# Adafruit_QT_Py_ESP32-S2.net
KiCad netlist of a schematic drawn in EAGLE
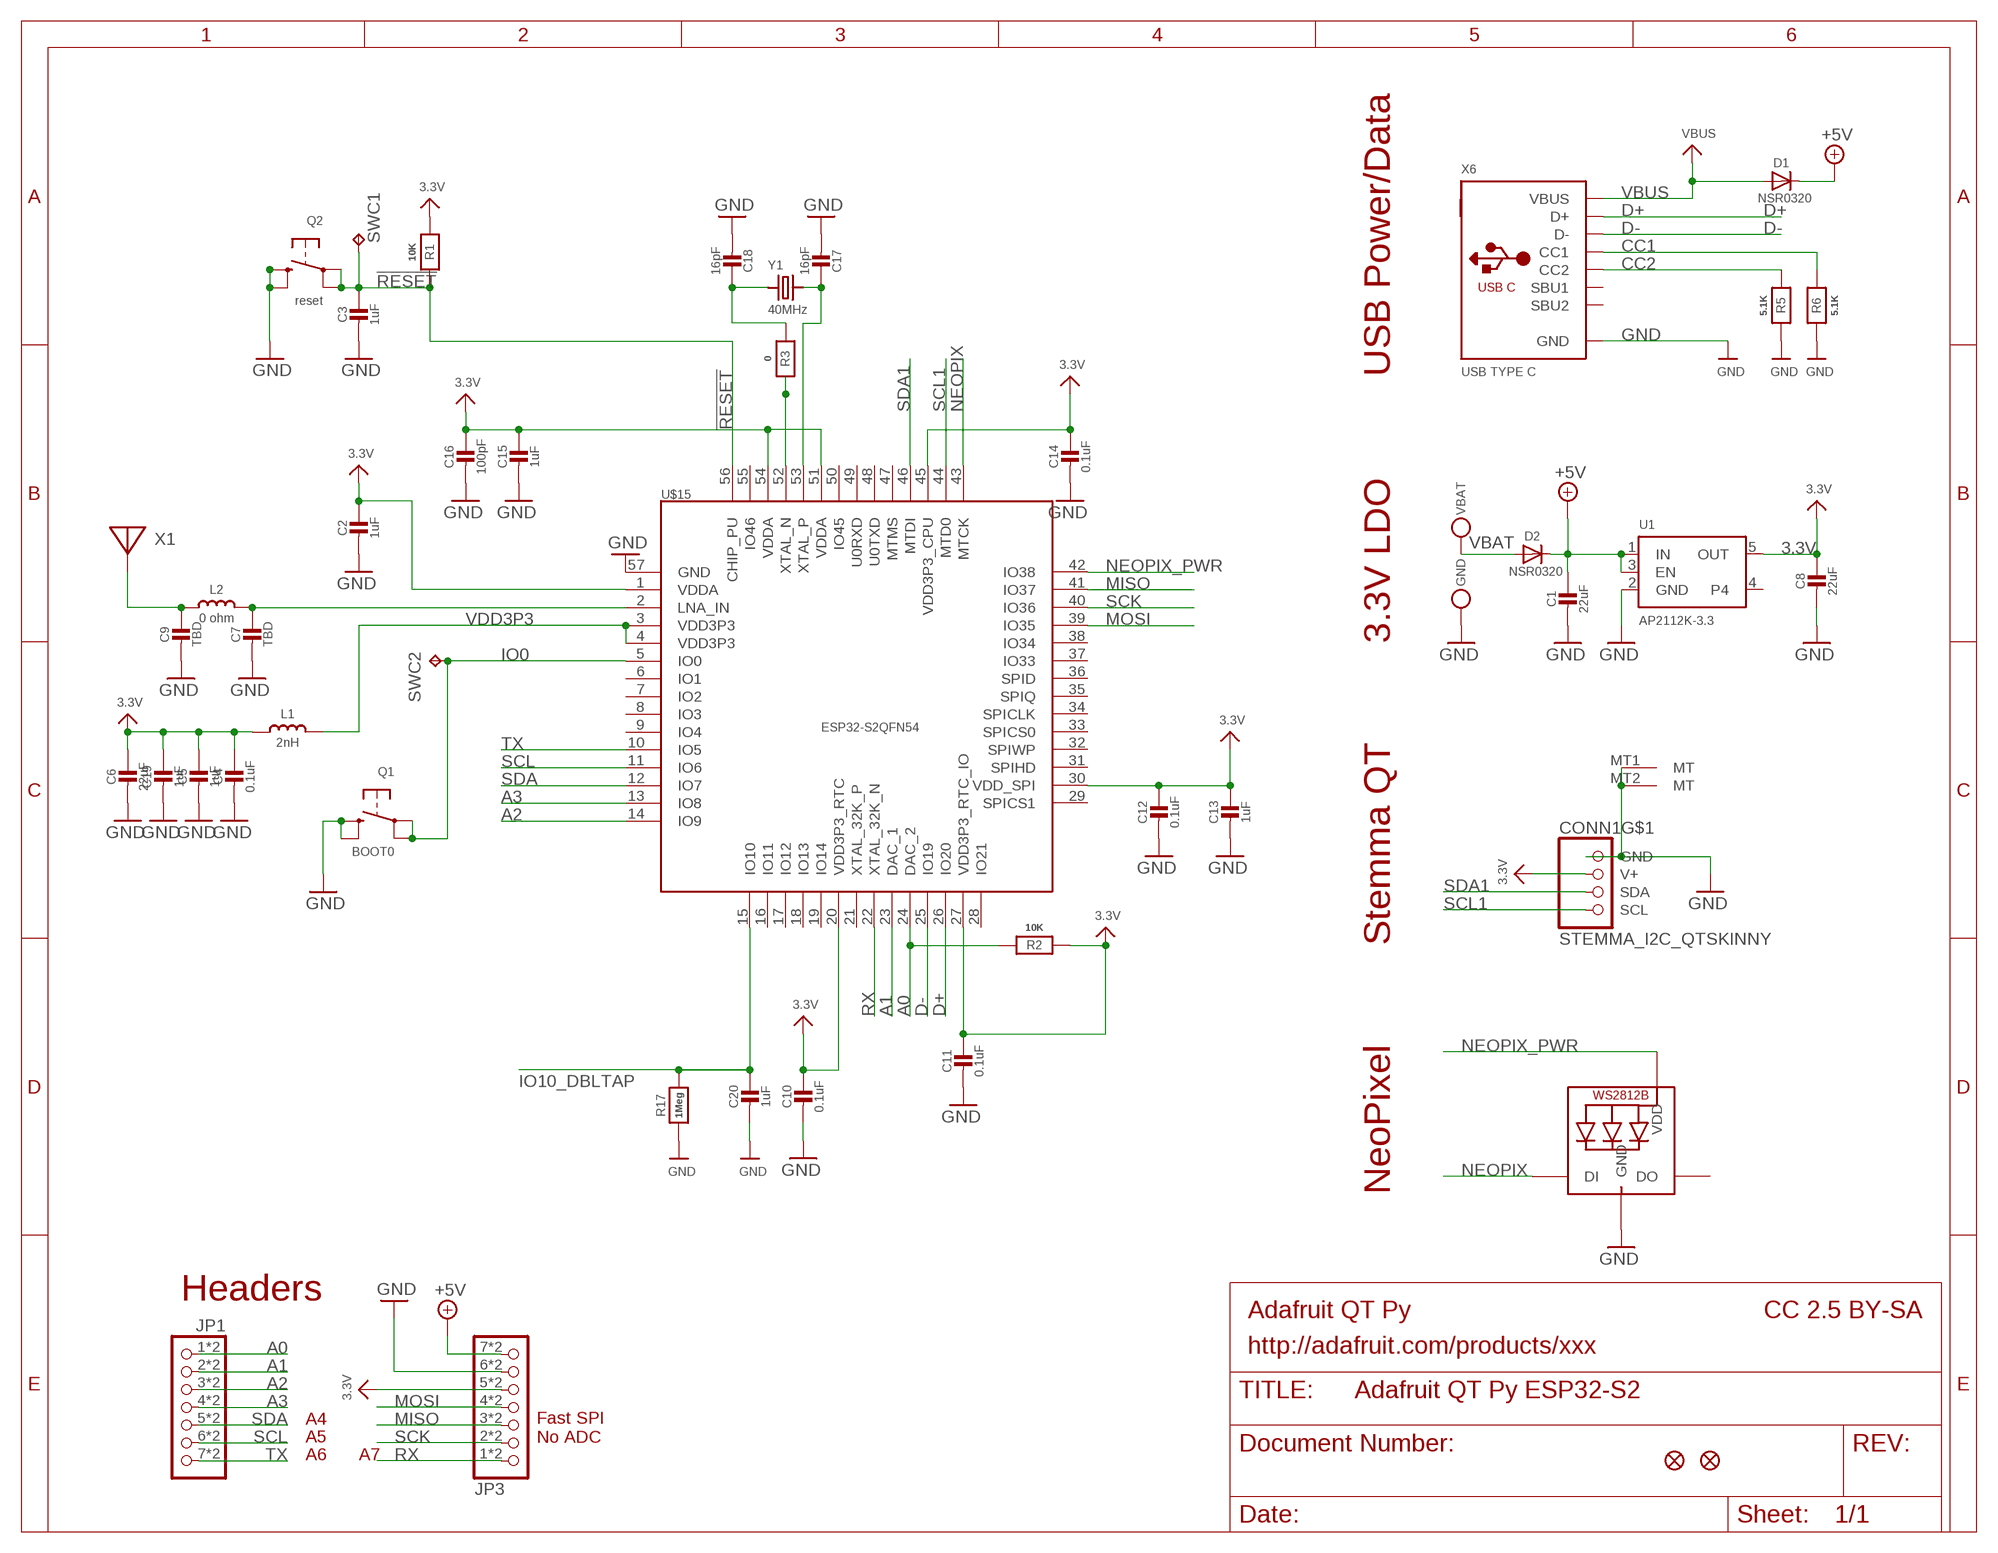
[diagram p0: schematic, sheet 1]

(export (version "E")
  (design (tool "Eeschema 10.0.6"))
  (components
    (comp (ref "C1")
      (value "22uF")
      (footprint "eagle-import:0805-NO")
      (libsource (lib "eagle-import") (part "CAP_CERAMIC0805-NOOUTLINE"))
    )
    (comp (ref "C2")
      (value "1uF")
      (footprint "eagle-import:_0402NO")
      (libsource (lib "eagle-import") (part "CAP_CERAMIC_0402NO"))
    )
    (comp (ref "C3")
      (value "1uF")
      (footprint "eagle-import:_0402NO")
      (libsource (lib "eagle-import") (part "CAP_CERAMIC_0402NO"))
    )
    (comp (ref "C4")
      (value "0.1uF")
      (footprint "eagle-import:_0402NO")
      (libsource (lib "eagle-import") (part "CAP_CERAMIC_0402NO"))
    )
    (comp (ref "C5")
      (value "1uF")
      (footprint "eagle-import:_0402NO")
      (libsource (lib "eagle-import") (part "CAP_CERAMIC_0402NO"))
    )
    (comp (ref "C6")
      (value "22uF")
      (footprint "eagle-import:0805-NO")
      (libsource (lib "eagle-import") (part "CAP_CERAMIC0805-NOOUTLINE"))
    )
    (comp (ref "C7")
      (value "TBD")
      (footprint "eagle-import:_0402NO")
      (libsource (lib "eagle-import") (part "CAP_CERAMIC_0402NO"))
    )
    (comp (ref "C8")
      (value "22uF")
      (footprint "eagle-import:0805-NO")
      (libsource (lib "eagle-import") (part "CAP_CERAMIC0805-NOOUTLINE"))
    )
    (comp (ref "C9")
      (value "TBD")
      (footprint "eagle-import:_0402NO")
      (libsource (lib "eagle-import") (part "CAP_CERAMIC_0402NO"))
    )
    (comp (ref "C10")
      (value "0.1uF")
      (footprint "eagle-import:_0402NO")
      (libsource (lib "eagle-import") (part "CAP_CERAMIC_0402NO"))
    )
    (comp (ref "C11")
      (value "0.1uF")
      (footprint "eagle-import:_0402NO")
      (libsource (lib "eagle-import") (part "CAP_CERAMIC_0402NO"))
    )
    (comp (ref "C12")
      (value "0.1uF")
      (footprint "eagle-import:_0402NO")
      (libsource (lib "eagle-import") (part "CAP_CERAMIC_0402NO"))
    )
    (comp (ref "C13")
      (value "1uF")
      (footprint "eagle-import:_0402NO")
      (libsource (lib "eagle-import") (part "CAP_CERAMIC_0402NO"))
    )
    (comp (ref "C14")
      (value "0.1uF")
      (footprint "eagle-import:_0402NO")
      (libsource (lib "eagle-import") (part "CAP_CERAMIC_0402NO"))
    )
    (comp (ref "C15")
      (value "1uF")
      (footprint "eagle-import:_0402NO")
      (libsource (lib "eagle-import") (part "CAP_CERAMIC_0402NO"))
    )
    (comp (ref "C16")
      (value "100pF")
      (footprint "eagle-import:_0402NO")
      (libsource (lib "eagle-import") (part "CAP_CERAMIC_0402NO"))
    )
    (comp (ref "C17")
      (value "16pF")
      (footprint "eagle-import:_0402NO")
      (libsource (lib "eagle-import") (part "CAP_CERAMIC_0402NO"))
    )
    (comp (ref "C18")
      (value "16pF")
      (footprint "eagle-import:_0402NO")
      (libsource (lib "eagle-import") (part "CAP_CERAMIC_0402NO"))
    )
    (comp (ref "C19")
      (value "1uF")
      (footprint "eagle-import:_0402NO")
      (libsource (lib "eagle-import") (part "CAP_CERAMIC_0402NO"))
    )
    (comp (ref "C20")
      (value "1uF")
      (footprint "eagle-import:_0402NO")
      (libsource (lib "eagle-import") (part "CAP_CERAMIC_0402NO"))
    )
    (comp (ref "CONN1")
      (value "STEMMA_I2C_QTSKINNY")
      (footprint "eagle-import:JST_SH4_SKINNY")
      (libsource (lib "eagle-import") (part "STEMMA_I2C_QTSKINNY"))
    )
    (comp (ref "D1")
      (value "NSR0320")
      (footprint "eagle-import:SOD-323_MINI")
      (libsource (lib "eagle-import") (part "DIODE_SOD323MINI"))
    )
    (comp (ref "D2")
      (value "NSR0320")
      (footprint "eagle-import:SOD-323_MINI")
      (libsource (lib "eagle-import") (part "DIODE_SOD323MINI"))
    )
    (comp (ref "GND")
      (value "TESTPOINT_1X3")
      (footprint "eagle-import:TESTPOINT_RECT_1X3MM")
      (libsource (lib "eagle-import") (part "TESTPOINT_1X3"))
    )
    (comp (ref "JP1")
      (value "HEADER-1X7_CASTEL")
      (footprint "eagle-import:1X07_CASTEL")
      (libsource (lib "eagle-import") (part "HEADER-1X7_CASTEL"))
    )
    (comp (ref "JP3")
      (value "HEADER-1X7_CASTEL")
      (footprint "eagle-import:1X07_CASTEL")
      (libsource (lib "eagle-import") (part "HEADER-1X7_CASTEL"))
    )
    (comp (ref "L1")
      (value "2nH")
      (footprint "eagle-import:_0402")
      (libsource (lib "eagle-import") (part "INDUCTOR_0402"))
    )
    (comp (ref "L2")
      (value "0 ohm")
      (footprint "eagle-import:_0402")
      (libsource (lib "eagle-import") (part "INDUCTOR_0402"))
    )
    (comp (ref "LED1")
      (value "WS2812B_SK6805_1515")
      (footprint "eagle-import:SK6805_1515")
      (libsource (lib "eagle-import") (part "WS2812B_SK6805_1515"))
    )
    (comp (ref "Q1")
      (value "BOOT0")
      (footprint "eagle-import:BTN_KMR2_4.6X2.8")
      (libsource (lib "eagle-import") (part "SWITCH_TACT_SMT4.6X2.8"))
    )
    (comp (ref "Q2")
      (value "reset")
      (footprint "eagle-import:BTN_KMR2_4.6X2.8")
      (libsource (lib "eagle-import") (part "SWITCH_TACT_SMT4.6X2.8"))
    )
    (comp (ref "R1")
      (value "10K")
      (footprint "eagle-import:_0402NO")
      (libsource (lib "eagle-import") (part "RESISTOR_0402NO"))
    )
    (comp (ref "R2")
      (value "10K")
      (footprint "eagle-import:_0402NO")
      (libsource (lib "eagle-import") (part "RESISTOR_0402NO"))
    )
    (comp (ref "R3")
      (value "0")
      (footprint "eagle-import:_0402NO")
      (libsource (lib "eagle-import") (part "RESISTOR_0402NO"))
    )
    (comp (ref "R5")
      (value "5.1K")
      (footprint "eagle-import:_0402NO")
      (libsource (lib "eagle-import") (part "RESISTOR_0402NO"))
    )
    (comp (ref "R6")
      (value "5.1K")
      (footprint "eagle-import:_0402NO")
      (libsource (lib "eagle-import") (part "RESISTOR_0402NO"))
    )
    (comp (ref "R17")
      (value "1Meg")
      (footprint "eagle-import:_0402NO")
      (libsource (lib "eagle-import") (part "RESISTOR_0402NO"))
    )
    (comp (ref "SWC1")
      (value "TPB1,27")
      (footprint "eagle-import:B1,27")
      (libsource (lib "eagle-import") (part "TPB1,27"))
    )
    (comp (ref "SWC2")
      (value "TPB1,27")
      (footprint "eagle-import:B1,27")
      (libsource (lib "eagle-import") (part "TPB1,27"))
    )
    (comp (ref "U$6")
      (value "FIDUCIAL_1MM")
      (footprint "eagle-import:FIDUCIAL_1MM")
      (libsource (lib "eagle-import") (part "FIDUCIAL_1MM"))
    )
    (comp (ref "U$8")
      (value "FIDUCIAL_1MM")
      (footprint "eagle-import:FIDUCIAL_1MM")
      (libsource (lib "eagle-import") (part "FIDUCIAL_1MM"))
    )
    (comp (ref "U$15")
      (value "ESP32-S2QFN54")
      (footprint "eagle-import:QFN40P700X700X90-57T400N")
      (fields
        (field (name "DIGI-KEY_PART_NUMBER") "1965-ESP32-S2CT-ND")
        (field (name "MF") "Espressif Systems")
        (field (name "MP") "ESP32-S2")
      )
      (libsource (lib "eagle-import") (part "ESP32-S2QFN54"))
    )
    (comp (ref "U1")
      (value "AP2112K-3.3")
      (footprint "eagle-import:SOT23-5")
      (libsource (lib "eagle-import") (part "VREG_SOT23-5"))
    )
    (comp (ref "VBAT")
      (value "TESTPOINT_1X3")
      (footprint "eagle-import:TESTPOINT_RECT_1X3MM")
      (libsource (lib "eagle-import") (part "TESTPOINT_1X3"))
    )
    (comp (ref "X1")
      (value "ANTENNA_JOHANSON_2450AT18B100")
      (footprint "eagle-import:ANT_2450AT18B100")
      (libsource (lib "eagle-import") (part "ANTENNA_JOHANSON_2450AT18B100"))
    )
    (comp (ref "X6")
      (value "USB TYPE C")
      (footprint "eagle-import:USB_C_CUSB31-CFM2AX-01-X")
      (libsource (lib "eagle-import") (part "USB_C"))
    )
    (comp (ref "Y1")
      (value "40MHz")
      (footprint "eagle-import:CRYSTAL_2X1.6")
      (libsource (lib "eagle-import") (part "CRYSTAL_2X1.6MM"))
    )
  )
  (nets
    (net (code "1") (name "+5V") (class "Default")
      (node (ref "C1") (pin "1") (pinfunction "1_1") (pintype "passive"))
      (node (ref "D1") (pin "C") (pinfunction "C_C") (pintype "passive"))
      (node (ref "D2") (pin "C") (pinfunction "C_C") (pintype "passive"))
      (node (ref "JP3") (pin "7") (pinfunction "7_7") (pintype "passive"))
      (node (ref "JP3") (pin "7C") (pinfunction "7_7C") (pintype "passive"))
      (node (ref "U1") (pin "1") (pinfunction "IN_1") (pintype "power_in"))
      (node (ref "U1") (pin "3") (pinfunction "EN_3") (pintype "input"))
    )
    (net (code "2") (name "/A0") (class "Default")
      (node (ref "JP1") (pin "1") (pinfunction "1_1") (pintype "passive"))
      (node (ref "JP1") (pin "1C") (pinfunction "1_1C") (pintype "passive"))
      (node (ref "R2") (pin "2") (pinfunction "2_2") (pintype "passive"))
      (node (ref "U$15") (pin "24") (pinfunction "DAC_2_24") (pintype "bidirectional"))
    )
    (net (code "3") (name "/A1") (class "Default")
      (node (ref "JP1") (pin "2") (pinfunction "2_2") (pintype "passive"))
      (node (ref "JP1") (pin "2C") (pinfunction "2_2C") (pintype "passive"))
      (node (ref "U$15") (pin "23") (pinfunction "DAC_1_23") (pintype "bidirectional"))
    )
    (net (code "4") (name "/A2") (class "Default")
      (node (ref "JP1") (pin "3") (pinfunction "3_3") (pintype "passive"))
      (node (ref "JP1") (pin "3C") (pinfunction "3_3C") (pintype "passive"))
      (node (ref "U$15") (pin "14") (pinfunction "IO9_14") (pintype "bidirectional"))
    )
    (net (code "5") (name "/A3") (class "Default")
      (node (ref "JP1") (pin "4") (pinfunction "4_4") (pintype "passive"))
      (node (ref "JP1") (pin "4C") (pinfunction "4_4C") (pintype "passive"))
      (node (ref "U$15") (pin "13") (pinfunction "IO8_13") (pintype "bidirectional"))
    )
    (net (code "6") (name "/CC1") (class "Default")
      (node (ref "R6") (pin "2") (pinfunction "2_2") (pintype "passive"))
      (node (ref "X6") (pin "A5") (pinfunction "CC1_A5") (pintype "bidirectional"))
    )
    (net (code "7") (name "/CC2") (class "Default")
      (node (ref "R5") (pin "2") (pinfunction "2_2") (pintype "passive"))
      (node (ref "X6") (pin "B5") (pinfunction "CC2_B5") (pintype "bidirectional"))
    )
    (net (code "8") (name "/D+") (class "Default")
      (node (ref "U$15") (pin "26") (pinfunction "IO20_26") (pintype "bidirectional"))
      (node (ref "X6") (pin "A6") (pinfunction "D+_A6") (pintype "bidirectional"))
      (node (ref "X6") (pin "B6") (pinfunction "D+_B6") (pintype "bidirectional"))
    )
    (net (code "9") (name "/D-") (class "Default")
      (node (ref "U$15") (pin "25") (pinfunction "IO19_25") (pintype "bidirectional"))
      (node (ref "X6") (pin "A7") (pinfunction "D-_A7") (pintype "bidirectional"))
      (node (ref "X6") (pin "B7") (pinfunction "D-_B7") (pintype "bidirectional"))
    )
    (net (code "10") (name "/IO0") (class "Default")
      (node (ref "Q1") (pin "A") (pinfunction "P_A") (pintype "passive"))
      (node (ref "Q1") (pin "A'") (pinfunction "P1_A'") (pintype "passive"))
      (node (ref "SWC2") (pin "TP") (pinfunction "TP_TP") (pintype "input"))
      (node (ref "U$15") (pin "5") (pinfunction "IO0_5") (pintype "bidirectional"))
    )
    (net (code "11") (name "/IO10_DBLTAP") (class "Default")
      (node (ref "C20") (pin "1") (pinfunction "1_1") (pintype "passive"))
      (node (ref "R17") (pin "2") (pinfunction "2_2") (pintype "passive"))
      (node (ref "U$15") (pin "15") (pinfunction "IO10_15") (pintype "bidirectional"))
    )
    (net (code "12") (name "/MISO") (class "Default")
      (node (ref "JP3") (pin "3") (pinfunction "3_3") (pintype "passive"))
      (node (ref "JP3") (pin "3C") (pinfunction "3_3C") (pintype "passive"))
      (node (ref "U$15") (pin "41") (pinfunction "IO37_41") (pintype "bidirectional"))
    )
    (net (code "13") (name "/MOSI") (class "Default")
      (node (ref "JP3") (pin "4") (pinfunction "4_4") (pintype "passive"))
      (node (ref "JP3") (pin "4C") (pinfunction "4_4C") (pintype "passive"))
      (node (ref "U$15") (pin "39") (pinfunction "IO35_39") (pintype "bidirectional"))
    )
    (net (code "14") (name "/NEOPIX") (class "Default")
      (node (ref "LED1") (pin "1") (pinfunction "DI_1") (pintype "input"))
      (node (ref "U$15") (pin "43") (pinfunction "MTCK_43") (pintype "bidirectional"))
    )
    (net (code "15") (name "/NEOPIX_PWR") (class "Default")
      (node (ref "LED1") (pin "2") (pinfunction "VDD_2") (pintype "power_in"))
      (node (ref "U$15") (pin "42") (pinfunction "IO38_42") (pintype "bidirectional"))
    )
    (net (code "16") (name "/RX") (class "Default")
      (node (ref "JP3") (pin "1") (pinfunction "1_1") (pintype "passive"))
      (node (ref "JP3") (pin "1C") (pinfunction "1_1C") (pintype "passive"))
      (node (ref "U$15") (pin "22") (pinfunction "XTAL_32K_N_22") (pintype "bidirectional"))
    )
    (net (code "17") (name "/SCK") (class "Default")
      (node (ref "JP3") (pin "2") (pinfunction "2_2") (pintype "passive"))
      (node (ref "JP3") (pin "2C") (pinfunction "2_2C") (pintype "passive"))
      (node (ref "U$15") (pin "40") (pinfunction "IO36_40") (pintype "bidirectional"))
    )
    (net (code "18") (name "/SCL") (class "Default")
      (node (ref "JP1") (pin "6") (pinfunction "6_6") (pintype "passive"))
      (node (ref "JP1") (pin "6C") (pinfunction "6_6C") (pintype "passive"))
      (node (ref "U$15") (pin "11") (pinfunction "IO6_11") (pintype "bidirectional"))
    )
    (net (code "19") (name "/SCL1") (class "Default")
      (node (ref "CONN1") (pin "4") (pinfunction "SCL_4") (pintype "passive"))
      (node (ref "U$15") (pin "44") (pinfunction "MTD0_44") (pintype "bidirectional"))
    )
    (net (code "20") (name "/SDA") (class "Default")
      (node (ref "JP1") (pin "5") (pinfunction "5_5") (pintype "passive"))
      (node (ref "JP1") (pin "5C") (pinfunction "5_5C") (pintype "passive"))
      (node (ref "U$15") (pin "12") (pinfunction "IO7_12") (pintype "bidirectional"))
    )
    (net (code "21") (name "/SDA1") (class "Default")
      (node (ref "CONN1") (pin "3") (pinfunction "SDA_3") (pintype "passive"))
      (node (ref "U$15") (pin "46") (pinfunction "MTDI_46") (pintype "bidirectional"))
    )
    (net (code "22") (name "/TX") (class "Default")
      (node (ref "JP1") (pin "7") (pinfunction "7_7") (pintype "passive"))
      (node (ref "JP1") (pin "7C") (pinfunction "7_7C") (pintype "passive"))
      (node (ref "U$15") (pin "10") (pinfunction "IO5_10") (pintype "bidirectional"))
    )
    (net (code "23") (name "/VBAT") (class "Default")
      (node (ref "D2") (pin "A") (pinfunction "A_A") (pintype "passive"))
      (node (ref "VBAT") (pin "P$1") (pinfunction "P$1_P$1") (pintype "bidirectional"))
    )
    (net (code "24") (name "/VDD3P3") (class "Default")
      (node (ref "L1") (pin "2") (pinfunction "2_2") (pintype "passive"))
      (node (ref "U$15") (pin "3") (pinfunction "VDD3P3_3") (pintype "power_in"))
      (node (ref "U$15") (pin "4") (pinfunction "VDD3P3_4") (pintype "power_in"))
    )
    (net (code "25") (name "/~{RESET}") (class "Default")
      (node (ref "C3") (pin "1") (pinfunction "1_1") (pintype "passive"))
      (node (ref "Q2") (pin "A") (pinfunction "P_A") (pintype "passive"))
      (node (ref "Q2") (pin "A'") (pinfunction "P1_A'") (pintype "passive"))
      (node (ref "R1") (pin "2") (pinfunction "2_2") (pintype "passive"))
      (node (ref "SWC1") (pin "TP") (pinfunction "TP_TP") (pintype "input"))
      (node (ref "U$15") (pin "56") (pinfunction "CHIP_PU_56") (pintype "input"))
    )
    (net (code "26") (name "3.3V") (class "Default")
      (node (ref "C10") (pin "1") (pinfunction "1_1") (pintype "passive"))
      (node (ref "C11") (pin "1") (pinfunction "1_1") (pintype "passive"))
      (node (ref "C12") (pin "1") (pinfunction "1_1") (pintype "passive"))
      (node (ref "C13") (pin "1") (pinfunction "1_1") (pintype "passive"))
      (node (ref "C14") (pin "1") (pinfunction "1_1") (pintype "passive"))
      (node (ref "C15") (pin "1") (pinfunction "1_1") (pintype "passive"))
      (node (ref "C16") (pin "1") (pinfunction "1_1") (pintype "passive"))
      (node (ref "C19") (pin "1") (pinfunction "1_1") (pintype "passive"))
      (node (ref "C2") (pin "1") (pinfunction "1_1") (pintype "passive"))
      (node (ref "C4") (pin "1") (pinfunction "1_1") (pintype "passive"))
      (node (ref "C5") (pin "1") (pinfunction "1_1") (pintype "passive"))
      (node (ref "C6") (pin "1") (pinfunction "1_1") (pintype "passive"))
      (node (ref "C8") (pin "1") (pinfunction "1_1") (pintype "passive"))
      (node (ref "CONN1") (pin "2") (pinfunction "V+_2") (pintype "passive"))
      (node (ref "JP3") (pin "5") (pinfunction "5_5") (pintype "passive"))
      (node (ref "JP3") (pin "5C") (pinfunction "5_5C") (pintype "passive"))
      (node (ref "L1") (pin "1") (pinfunction "1_1") (pintype "passive"))
      (node (ref "R1") (pin "1") (pinfunction "1_1") (pintype "passive"))
      (node (ref "R2") (pin "1") (pinfunction "1_1") (pintype "passive"))
      (node (ref "U$15") (pin "1") (pinfunction "VDDA_1") (pintype "power_in"))
      (node (ref "U$15") (pin "20") (pinfunction "VDD3P3_RTC_20") (pintype "power_in"))
      (node (ref "U$15") (pin "27") (pinfunction "VDD3P3_RTC_IO_27") (pintype "power_in"))
      (node (ref "U$15") (pin "30") (pinfunction "VDD_SPI_30") (pintype "power_in"))
      (node (ref "U$15") (pin "45") (pinfunction "VDD3P3_CPU_45") (pintype "power_in"))
      (node (ref "U$15") (pin "51") (pinfunction "VDDA_51") (pintype "power_in"))
      (node (ref "U$15") (pin "54") (pinfunction "VDDA_54") (pintype "power_in"))
      (node (ref "U1") (pin "5") (pinfunction "OUT_5") (pintype "power_in"))
    )
    (net (code "27") (name "GND") (class "Default")
      (node (ref "C1") (pin "2") (pinfunction "2_2") (pintype "passive"))
      (node (ref "C10") (pin "2") (pinfunction "2_2") (pintype "passive"))
      (node (ref "C11") (pin "2") (pinfunction "2_2") (pintype "passive"))
      (node (ref "C12") (pin "2") (pinfunction "2_2") (pintype "passive"))
      (node (ref "C13") (pin "2") (pinfunction "2_2") (pintype "passive"))
      (node (ref "C14") (pin "2") (pinfunction "2_2") (pintype "passive"))
      (node (ref "C15") (pin "2") (pinfunction "2_2") (pintype "passive"))
      (node (ref "C16") (pin "2") (pinfunction "2_2") (pintype "passive"))
      (node (ref "C17") (pin "2") (pinfunction "2_2") (pintype "passive"))
      (node (ref "C18") (pin "2") (pinfunction "2_2") (pintype "passive"))
      (node (ref "C19") (pin "2") (pinfunction "2_2") (pintype "passive"))
      (node (ref "C2") (pin "2") (pinfunction "2_2") (pintype "passive"))
      (node (ref "C20") (pin "2") (pinfunction "2_2") (pintype "passive"))
      (node (ref "C3") (pin "2") (pinfunction "2_2") (pintype "passive"))
      (node (ref "C4") (pin "2") (pinfunction "2_2") (pintype "passive"))
      (node (ref "C5") (pin "2") (pinfunction "2_2") (pintype "passive"))
      (node (ref "C6") (pin "2") (pinfunction "2_2") (pintype "passive"))
      (node (ref "C7") (pin "2") (pinfunction "2_2") (pintype "passive"))
      (node (ref "C8") (pin "2") (pinfunction "2_2") (pintype "passive"))
      (node (ref "C9") (pin "2") (pinfunction "2_2") (pintype "passive"))
      (node (ref "CONN1") (pin "1") (pinfunction "GND_1") (pintype "passive"))
      (node (ref "CONN1") (pin "MT1") (pinfunction "MT_MT1") (pintype "bidirectional"))
      (node (ref "CONN1") (pin "MT2") (pinfunction "MT_MT2") (pintype "bidirectional"))
      (node (ref "GND") (pin "P$1") (pinfunction "P$1_P$1") (pintype "bidirectional"))
      (node (ref "JP3") (pin "6") (pinfunction "6_6") (pintype "passive"))
      (node (ref "JP3") (pin "6C") (pinfunction "6_6C") (pintype "passive"))
      (node (ref "LED1") (pin "4") (pinfunction "GND_4") (pintype "power_in"))
      (node (ref "Q1") (pin "B") (pinfunction "S_B") (pintype "passive"))
      (node (ref "Q1") (pin "B'") (pinfunction "S1_B'") (pintype "passive"))
      (node (ref "Q2") (pin "B") (pinfunction "S_B") (pintype "passive"))
      (node (ref "Q2") (pin "B'") (pinfunction "S1_B'") (pintype "passive"))
      (node (ref "R17") (pin "1") (pinfunction "1_1") (pintype "passive"))
      (node (ref "R5") (pin "1") (pinfunction "1_1") (pintype "passive"))
      (node (ref "R6") (pin "1") (pinfunction "1_1") (pintype "passive"))
      (node (ref "U$15") (pin "57") (pinfunction "GND_57") (pintype "power_in"))
      (node (ref "U1") (pin "2") (pinfunction "GND_2") (pintype "power_in"))
      (node (ref "X6") (pin "A1B12") (pinfunction "GND_A1B12") (pintype "power_in"))
      (node (ref "X6") (pin "B1A12") (pinfunction "GND_B1A12") (pintype "power_in"))
    )
    (net (code "28") (name "Net-(C18-Pad1)") (class "Default")
      (node (ref "C18") (pin "1") (pinfunction "1_1") (pintype "passive"))
      (node (ref "R3") (pin "1") (pinfunction "1_1") (pintype "passive"))
      (node (ref "Y1") (pin "1") (pinfunction "1_1") (pintype "passive"))
    )
    (net (code "29") (name "Net-(U$15-LNA_IN)") (class "Default")
      (node (ref "C7") (pin "1") (pinfunction "1_1") (pintype "passive"))
      (node (ref "L2") (pin "2") (pinfunction "2_2") (pintype "passive"))
      (node (ref "U$15") (pin "2") (pinfunction "LNA_IN_2") (pintype "bidirectional"))
    )
    (net (code "30") (name "Net-(U$15-XTAL_N)") (class "Default")
      (node (ref "R3") (pin "2") (pinfunction "2_2") (pintype "passive"))
      (node (ref "U$15") (pin "52") (pinfunction "XTAL_N_52") (pintype "bidirectional"))
    )
    (net (code "31") (name "Net-(U$15-XTAL_P)") (class "Default")
      (node (ref "C17") (pin "1") (pinfunction "1_1") (pintype "passive"))
      (node (ref "U$15") (pin "53") (pinfunction "XTAL_P_53") (pintype "bidirectional"))
      (node (ref "Y1") (pin "3") (pinfunction "2_3") (pintype "passive"))
    )
    (net (code "32") (name "Net-(X1-P$1)") (class "Default")
      (node (ref "C9") (pin "1") (pinfunction "1_1") (pintype "passive"))
      (node (ref "L2") (pin "1") (pinfunction "1_1") (pintype "passive"))
      (node (ref "X1") (pin "FP") (pinfunction "P$1_FP") (pintype "passive"))
    )
    (net (code "33") (name "VBUS") (class "Default")
      (node (ref "D1") (pin "A") (pinfunction "A_A") (pintype "passive"))
      (node (ref "X6") (pin "A4B9") (pinfunction "VBUS_A4B9") (pintype "power_in"))
      (node (ref "X6") (pin "B4A9") (pinfunction "VBUS_B4A9") (pintype "power_in"))
    )
    (net (code "34") (name "unconnected-(LED1-DO-Pad3)") (class "Default")
      (node (ref "LED1") (pin "3") (pinfunction "DO_3") (pintype "output"))
    )
    (net (code "35") (name "unconnected-(U$15-IO1-Pad6)") (class "Default")
      (node (ref "U$15") (pin "6") (pinfunction "IO1_6") (pintype "bidirectional"))
    )
    (net (code "36") (name "unconnected-(U$15-IO2-Pad7)") (class "Default")
      (node (ref "U$15") (pin "7") (pinfunction "IO2_7") (pintype "bidirectional"))
    )
    (net (code "37") (name "unconnected-(U$15-IO3-Pad8)") (class "Default")
      (node (ref "U$15") (pin "8") (pinfunction "IO3_8") (pintype "bidirectional"))
    )
    (net (code "38") (name "unconnected-(U$15-IO4-Pad9)") (class "Default")
      (node (ref "U$15") (pin "9") (pinfunction "IO4_9") (pintype "bidirectional"))
    )
    (net (code "39") (name "unconnected-(U$15-IO11-Pad16)") (class "Default")
      (node (ref "U$15") (pin "16") (pinfunction "IO11_16") (pintype "bidirectional"))
    )
    (net (code "40") (name "unconnected-(U$15-IO12-Pad17)") (class "Default")
      (node (ref "U$15") (pin "17") (pinfunction "IO12_17") (pintype "bidirectional"))
    )
    (net (code "41") (name "unconnected-(U$15-IO13-Pad18)") (class "Default")
      (node (ref "U$15") (pin "18") (pinfunction "IO13_18") (pintype "bidirectional"))
    )
    (net (code "42") (name "unconnected-(U$15-IO14-Pad19)") (class "Default")
      (node (ref "U$15") (pin "19") (pinfunction "IO14_19") (pintype "bidirectional"))
    )
    (net (code "43") (name "unconnected-(U$15-IO21-Pad28)") (class "Default")
      (node (ref "U$15") (pin "28") (pinfunction "IO21_28") (pintype "bidirectional"))
    )
    (net (code "44") (name "unconnected-(U$15-IO33-Pad37)") (class "Default")
      (node (ref "U$15") (pin "37") (pinfunction "IO33_37") (pintype "bidirectional"))
    )
    (net (code "45") (name "unconnected-(U$15-IO34-Pad38)") (class "Default")
      (node (ref "U$15") (pin "38") (pinfunction "IO34_38") (pintype "bidirectional"))
    )
    (net (code "46") (name "unconnected-(U$15-IO45-Pad50)") (class "Default")
      (node (ref "U$15") (pin "50") (pinfunction "IO45_50") (pintype "bidirectional"))
    )
    (net (code "47") (name "unconnected-(U$15-IO46-Pad55)") (class "Default")
      (node (ref "U$15") (pin "55") (pinfunction "IO46_55") (pintype "input"))
    )
    (net (code "48") (name "unconnected-(U$15-MTMS-Pad47)") (class "Default")
      (node (ref "U$15") (pin "47") (pinfunction "MTMS_47") (pintype "bidirectional"))
    )
    (net (code "49") (name "unconnected-(U$15-SPICLK-Pad34)") (class "Default")
      (node (ref "U$15") (pin "34") (pinfunction "SPICLK_34") (pintype "bidirectional"))
    )
    (net (code "50") (name "unconnected-(U$15-SPICS0-Pad33)") (class "Default")
      (node (ref "U$15") (pin "33") (pinfunction "SPICS0_33") (pintype "bidirectional"))
    )
    (net (code "51") (name "unconnected-(U$15-SPICS1-Pad29)") (class "Default")
      (node (ref "U$15") (pin "29") (pinfunction "SPICS1_29") (pintype "bidirectional"))
    )
    (net (code "52") (name "unconnected-(U$15-SPID-Pad36)") (class "Default")
      (node (ref "U$15") (pin "36") (pinfunction "SPID_36") (pintype "bidirectional"))
    )
    (net (code "53") (name "unconnected-(U$15-SPIHD-Pad31)") (class "Default")
      (node (ref "U$15") (pin "31") (pinfunction "SPIHD_31") (pintype "bidirectional"))
    )
    (net (code "54") (name "unconnected-(U$15-SPIQ-Pad35)") (class "Default")
      (node (ref "U$15") (pin "35") (pinfunction "SPIQ_35") (pintype "bidirectional"))
    )
    (net (code "55") (name "unconnected-(U$15-SPIWP-Pad32)") (class "Default")
      (node (ref "U$15") (pin "32") (pinfunction "SPIWP_32") (pintype "bidirectional"))
    )
    (net (code "56") (name "unconnected-(U$15-U0RXD-Pad49)") (class "Default")
      (node (ref "U$15") (pin "49") (pinfunction "U0RXD_49") (pintype "bidirectional"))
    )
    (net (code "57") (name "unconnected-(U$15-U0TXD-Pad48)") (class "Default")
      (node (ref "U$15") (pin "48") (pinfunction "U0TXD_48") (pintype "bidirectional"))
    )
    (net (code "58") (name "unconnected-(U$15-XTAL_32K_P-Pad21)") (class "Default")
      (node (ref "U$15") (pin "21") (pinfunction "XTAL_32K_P_21") (pintype "bidirectional"))
    )
    (net (code "59") (name "unconnected-(U1-P4-Pad4)") (class "Default")
      (node (ref "U1") (pin "4") (pinfunction "P4_4") (pintype "bidirectional"))
    )
    (net (code "60") (name "unconnected-(X6-SBU1-PadA8)") (class "Default")
      (node (ref "X6") (pin "A8") (pinfunction "SBU1_A8") (pintype "bidirectional"))
    )
    (net (code "61") (name "unconnected-(X6-SBU2-PadB8)") (class "Default")
      (node (ref "X6") (pin "B8") (pinfunction "SBU2_B8") (pintype "bidirectional"))
    )
  )
)
